# wssf_arduino_nano_client.net
KiCad netlist of a schematic drawn in EAGLE
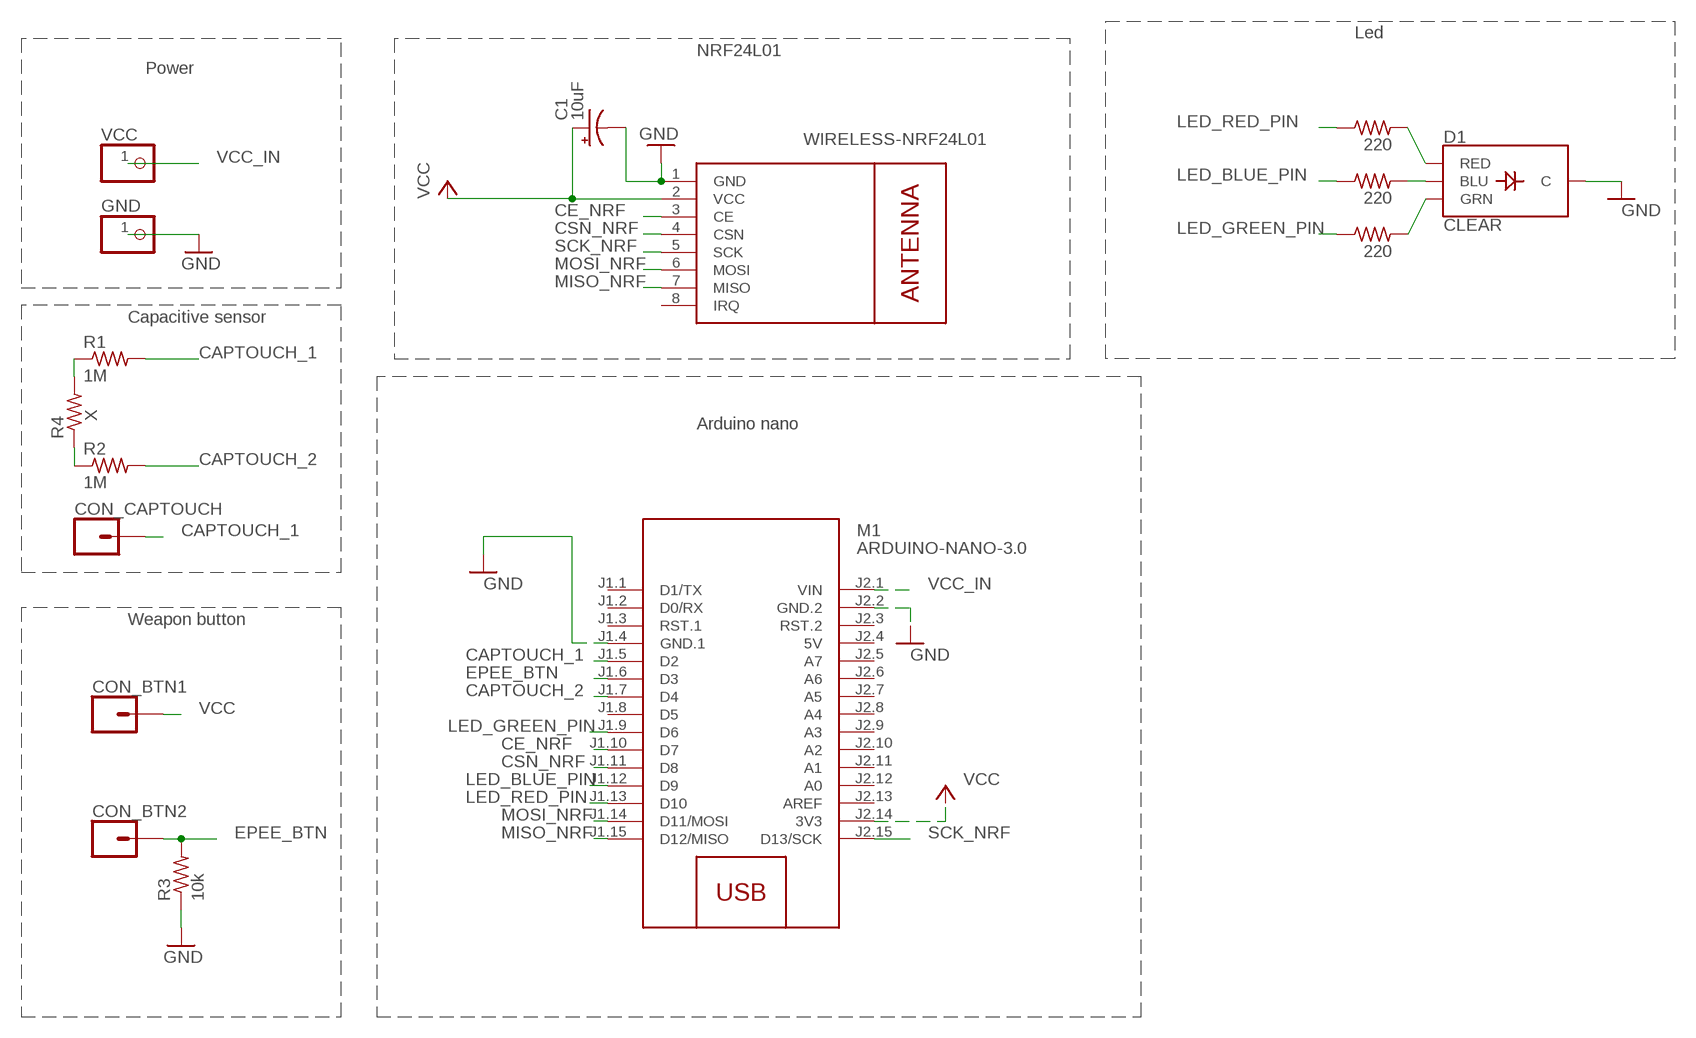
[diagram p0: schematic, sheet 1]

(export (version "E")
  (design (tool "Eeschema 10.0.6"))
  (components
    (comp (ref "C1")
      (value "10uF")
      (footprint "eagle-import:E2-5")
      (libsource (lib "eagle-import") (part "CPOL-USE2-5"))
    )
    (comp (ref "CON_BTN1")
      (value "CONN_01")
      (footprint "eagle-import:1X01")
      (libsource (lib "eagle-import") (part "CONN_01"))
    )
    (comp (ref "CON_BTN2")
      (value "CONN_01")
      (footprint "eagle-import:1X01")
      (libsource (lib "eagle-import") (part "CONN_01"))
    )
    (comp (ref "CON_CAPTOUCH")
      (value "CONN_01")
      (footprint "eagle-import:1X01")
      (libsource (lib "eagle-import") (part "CONN_01"))
    )
    (comp (ref "D1")
      (value "CLEAR")
      (footprint "eagle-import:LED-RGB-THRU")
      (libsource (lib "eagle-import") (part "LED-RGB-CCCLEAR"))
    )
    (comp (ref "GND")
      (value "PINHD-1X1")
      (footprint "eagle-import:1X01")
      (libsource (lib "eagle-import") (part "PINHD-1X1"))
    )
    (comp (ref "M1")
      (value "ARDUINO-NANO-3.0")
      (footprint "eagle-import:ARDUINO-NANO-3.0")
      (libsource (lib "eagle-import") (part "ARDUINO-NANO-3.0"))
    )
    (comp (ref "M2")
      (value "WIRELESS-NRF24L01")
      (footprint "eagle-import:WIRELESS-NRF24L01")
      (libsource (lib "eagle-import") (part "WIRELESS-NRF24L01"))
    )
    (comp (ref "R1")
      (value "1M")
      (footprint "eagle-import:0204_7")
      (libsource (lib "eagle-import") (part "R-US_0204/7"))
    )
    (comp (ref "R2")
      (value "1M")
      (footprint "eagle-import:0204_7")
      (libsource (lib "eagle-import") (part "R-US_0204/7"))
    )
    (comp (ref "R3")
      (value "10k")
      (footprint "eagle-import:0204_7")
      (libsource (lib "eagle-import") (part "R-US_0204/7"))
    )
    (comp (ref "R4")
      (value "X")
      (footprint "eagle-import:0204_7")
      (libsource (lib "eagle-import") (part "R-US_0204/7"))
    )
    (comp (ref "R_LED1")
      (value "220")
      (footprint "eagle-import:0204_7")
      (libsource (lib "eagle-import") (part "R-US_0204/7"))
    )
    (comp (ref "R_LED2")
      (value "220")
      (footprint "eagle-import:0204_7")
      (libsource (lib "eagle-import") (part "R-US_0204/7"))
    )
    (comp (ref "R_LED3")
      (value "220")
      (footprint "eagle-import:0204_7")
      (libsource (lib "eagle-import") (part "R-US_0204/7"))
    )
    (comp (ref "VCC")
      (value "PINHD-1X1")
      (footprint "eagle-import:1X01")
      (libsource (lib "eagle-import") (part "PINHD-1X1"))
    )
  )
  (nets
    (net (code "1") (name "/5V") (class "Default")
      (node (ref "M1") (pin "J2.4") (pinfunction "5V_J2.4") (pintype "power_in"))
    )
    (net (code "2") (name "/CAPTOUCH_1") (class "Default")
      (node (ref "CON_CAPTOUCH") (pin "1") (pinfunction "1_1") (pintype "passive"))
      (node (ref "M1") (pin "J1.5") (pinfunction "D2_J1.5") (pintype "bidirectional"))
      (node (ref "R1") (pin "2") (pinfunction "2_2") (pintype "passive"))
    )
    (net (code "3") (name "/CAPTOUCH_2") (class "Default")
      (node (ref "M1") (pin "J1.7") (pinfunction "D4_J1.7") (pintype "bidirectional"))
      (node (ref "R2") (pin "2") (pinfunction "2_2") (pintype "passive"))
    )
    (net (code "4") (name "/CE_NRF") (class "Default")
      (node (ref "M1") (pin "J1.10") (pinfunction "D7_J1.10") (pintype "bidirectional"))
      (node (ref "M2") (pin "3") (pinfunction "CE_3") (pintype "bidirectional"))
    )
    (net (code "5") (name "/CSN_NRF") (class "Default")
      (node (ref "M1") (pin "J1.11") (pinfunction "D8_J1.11") (pintype "bidirectional"))
      (node (ref "M2") (pin "4") (pinfunction "CSN_4") (pintype "bidirectional"))
    )
    (net (code "6") (name "/EPEE_BTN") (class "Default")
      (node (ref "CON_BTN2") (pin "1") (pinfunction "1_1") (pintype "passive"))
      (node (ref "M1") (pin "J1.6") (pinfunction "D3_J1.6") (pintype "bidirectional"))
      (node (ref "R3") (pin "2") (pinfunction "2_2") (pintype "passive"))
    )
    (net (code "7") (name "/LED_BLUE_PIN") (class "Default")
      (node (ref "M1") (pin "J1.12") (pinfunction "D9_J1.12") (pintype "bidirectional"))
      (node (ref "R_LED2") (pin "1") (pinfunction "1_1") (pintype "passive"))
    )
    (net (code "8") (name "/LED_GREEN_PIN") (class "Default")
      (node (ref "M1") (pin "J1.9") (pinfunction "D6_J1.9") (pintype "bidirectional"))
      (node (ref "R_LED3") (pin "1") (pinfunction "1_1") (pintype "passive"))
    )
    (net (code "9") (name "/LED_RED_PIN") (class "Default")
      (node (ref "M1") (pin "J1.13") (pinfunction "D10_J1.13") (pintype "bidirectional"))
      (node (ref "R_LED1") (pin "1") (pinfunction "1_1") (pintype "passive"))
    )
    (net (code "10") (name "/MISO_NRF") (class "Default")
      (node (ref "M1") (pin "J1.15") (pinfunction "D12/MISO_J1.15") (pintype "bidirectional"))
      (node (ref "M2") (pin "7") (pinfunction "MISO_7") (pintype "bidirectional"))
    )
    (net (code "11") (name "/MOSI_NRF") (class "Default")
      (node (ref "M1") (pin "J1.14") (pinfunction "D11/MOSI_J1.14") (pintype "bidirectional"))
      (node (ref "M2") (pin "6") (pinfunction "MOSI_6") (pintype "bidirectional"))
    )
    (net (code "12") (name "/SCK_NRF") (class "Default")
      (node (ref "M1") (pin "J2.15") (pinfunction "D13/SCK_J2.15") (pintype "bidirectional"))
      (node (ref "M2") (pin "5") (pinfunction "SCK_5") (pintype "bidirectional"))
    )
    (net (code "13") (name "/VCC_IN") (class "Default")
      (node (ref "M1") (pin "J2.1") (pinfunction "VIN_J2.1") (pintype "power_in"))
      (node (ref "VCC") (pin "1") (pinfunction "1_1") (pintype "passive"))
    )
    (net (code "14") (name "GND") (class "Default")
      (node (ref "C1") (pin "-") (pinfunction "-_-") (pintype "passive"))
      (node (ref "D1") (pin "2") (pinfunction "C_2") (pintype "bidirectional"))
      (node (ref "GND") (pin "1") (pinfunction "1_1") (pintype "passive"))
      (node (ref "M1") (pin "J1.4") (pinfunction "GND.1_J1.4") (pintype "power_in"))
      (node (ref "M1") (pin "J2.2") (pinfunction "GND.2_J2.2") (pintype "power_in"))
      (node (ref "M2") (pin "1") (pinfunction "GND_1") (pintype "power_in"))
      (node (ref "R3") (pin "1") (pinfunction "1_1") (pintype "passive"))
    )
    (net (code "15") (name "Net-(D1-BLU)") (class "Default")
      (node (ref "D1") (pin "4") (pinfunction "BLU_4") (pintype "bidirectional"))
      (node (ref "R_LED2") (pin "2") (pinfunction "2_2") (pintype "passive"))
    )
    (net (code "16") (name "Net-(D1-GRN)") (class "Default")
      (node (ref "D1") (pin "3") (pinfunction "GRN_3") (pintype "bidirectional"))
      (node (ref "R_LED3") (pin "2") (pinfunction "2_2") (pintype "passive"))
    )
    (net (code "17") (name "Net-(D1-RED)") (class "Default")
      (node (ref "D1") (pin "1") (pinfunction "RED_1") (pintype "bidirectional"))
      (node (ref "R_LED1") (pin "2") (pinfunction "2_2") (pintype "passive"))
    )
    (net (code "18") (name "Net-(R1-Pad1)") (class "Default")
      (node (ref "R1") (pin "1") (pinfunction "1_1") (pintype "passive"))
      (node (ref "R4") (pin "2") (pinfunction "2_2") (pintype "passive"))
    )
    (net (code "19") (name "Net-(R2-Pad1)") (class "Default")
      (node (ref "R2") (pin "1") (pinfunction "1_1") (pintype "passive"))
      (node (ref "R4") (pin "1") (pinfunction "1_1") (pintype "passive"))
    )
    (net (code "20") (name "VCC") (class "Default")
      (node (ref "C1") (pin "+") (pinfunction "+_+") (pintype "passive"))
      (node (ref "CON_BTN1") (pin "1") (pinfunction "1_1") (pintype "passive"))
      (node (ref "M1") (pin "J2.14") (pinfunction "3V3_J2.14") (pintype "power_in"))
      (node (ref "M2") (pin "2") (pinfunction "VCC_2") (pintype "power_in"))
    )
    (net (code "21") (name "unconnected-(M1-A0-PadJ2.12)") (class "Default")
      (node (ref "M1") (pin "J2.12") (pinfunction "A0_J2.12") (pintype "bidirectional"))
    )
    (net (code "22") (name "unconnected-(M1-A1-PadJ2.11)") (class "Default")
      (node (ref "M1") (pin "J2.11") (pinfunction "A1_J2.11") (pintype "bidirectional"))
    )
    (net (code "23") (name "unconnected-(M1-A2-PadJ2.10)") (class "Default")
      (node (ref "M1") (pin "J2.10") (pinfunction "A2_J2.10") (pintype "bidirectional"))
    )
    (net (code "24") (name "unconnected-(M1-A3-PadJ2.9)") (class "Default")
      (node (ref "M1") (pin "J2.9") (pinfunction "A3_J2.9") (pintype "bidirectional"))
    )
    (net (code "25") (name "unconnected-(M1-A4-PadJ2.8)") (class "Default")
      (node (ref "M1") (pin "J2.8") (pinfunction "A4_J2.8") (pintype "bidirectional"))
    )
    (net (code "26") (name "unconnected-(M1-A5-PadJ2.7)") (class "Default")
      (node (ref "M1") (pin "J2.7") (pinfunction "A5_J2.7") (pintype "bidirectional"))
    )
    (net (code "27") (name "unconnected-(M1-A6-PadJ2.6)") (class "Default")
      (node (ref "M1") (pin "J2.6") (pinfunction "A6_J2.6") (pintype "bidirectional"))
    )
    (net (code "28") (name "unconnected-(M1-A7-PadJ2.5)") (class "Default")
      (node (ref "M1") (pin "J2.5") (pinfunction "A7_J2.5") (pintype "bidirectional"))
    )
    (net (code "29") (name "unconnected-(M1-AREF-PadJ2.13)") (class "Default")
      (node (ref "M1") (pin "J2.13") (pinfunction "AREF_J2.13") (pintype "bidirectional"))
    )
    (net (code "30") (name "unconnected-(M1-D0{slash}RX-PadJ1.2)") (class "Default")
      (node (ref "M1") (pin "J1.2") (pinfunction "D0/RX_J1.2") (pintype "bidirectional"))
    )
    (net (code "31") (name "unconnected-(M1-D1{slash}TX-PadJ1.1)") (class "Default")
      (node (ref "M1") (pin "J1.1") (pinfunction "D1/TX_J1.1") (pintype "bidirectional"))
    )
    (net (code "32") (name "unconnected-(M1-D5-PadJ1.8)") (class "Default")
      (node (ref "M1") (pin "J1.8") (pinfunction "D5_J1.8") (pintype "bidirectional"))
    )
    (net (code "33") (name "unconnected-(M1-RST.1-PadJ1.3)") (class "Default")
      (node (ref "M1") (pin "J1.3") (pinfunction "RST.1_J1.3") (pintype "bidirectional"))
    )
    (net (code "34") (name "unconnected-(M1-RST.2-PadJ2.3)") (class "Default")
      (node (ref "M1") (pin "J2.3") (pinfunction "RST.2_J2.3") (pintype "bidirectional"))
    )
    (net (code "35") (name "unconnected-(M2-IRQ-Pad8)") (class "Default")
      (node (ref "M2") (pin "8") (pinfunction "IRQ_8") (pintype "bidirectional"))
    )
  )
)
